# MCU.net
KiCad netlist of a schematic drawn in Altium Designer
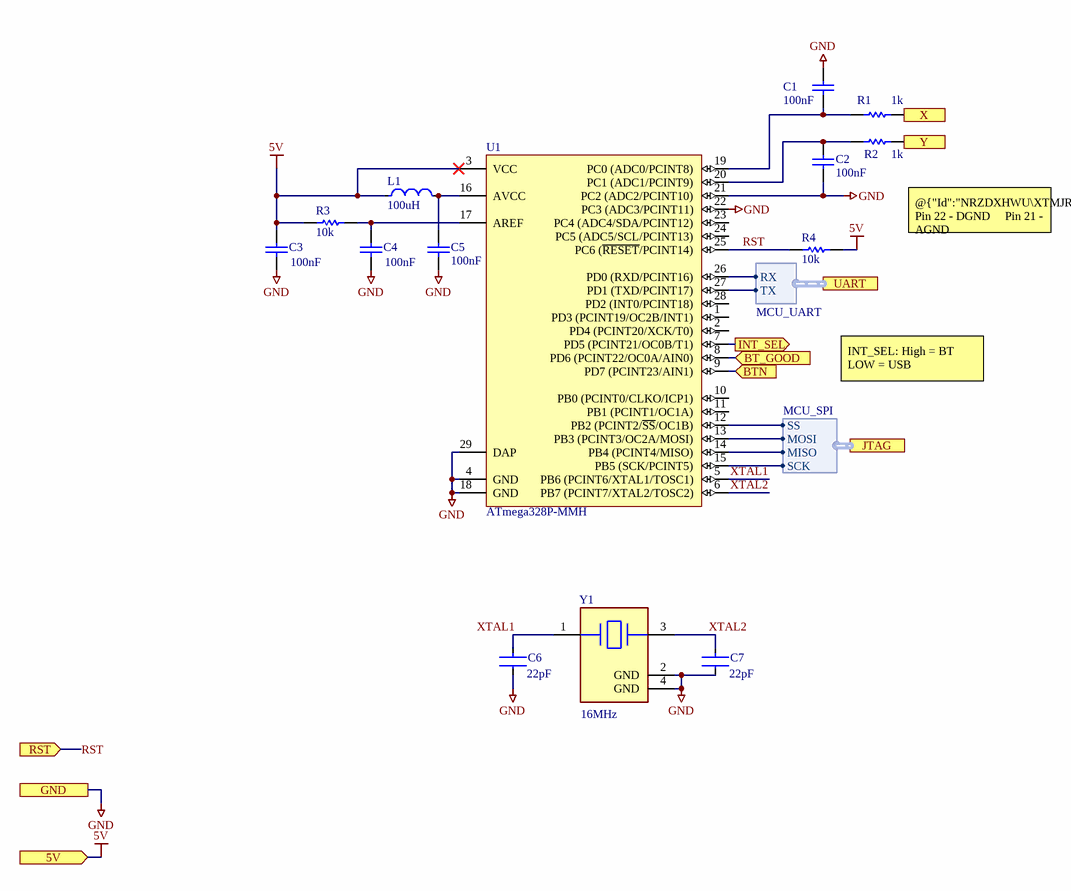
[diagram p0: MCU.SchDoc]

(export (version "E")
  (design (tool "Eeschema 10.0.6"))
  (components
    (comp (ref "C1")
      (value "100nF")
      (footprint "CAPC1005X56X25ML10T15")
      (fields
        (field (name "MANUFACTURER") "AVX Interconnect / Elco")
        (field (name "PART NUMBER") "0402YG104ZAT2A")
      )
      (libsource (lib "Altium Content Vault") (part "CAP"))
    )
    (comp (ref "C2")
      (value "100nF")
      (footprint "CAPC1005X56X25ML10T15")
      (fields
        (field (name "MANUFACTURER") "AVX Interconnect / Elco")
        (field (name "PART NUMBER") "0402YG104ZAT2A")
      )
      (libsource (lib "Altium Content Vault") (part "CAP"))
    )
    (comp (ref "C3")
      (value "100nF")
      (footprint "CAPC1005X56X25ML10T15")
      (fields
        (field (name "MANUFACTURER") "AVX Interconnect / Elco")
        (field (name "PART NUMBER") "0402YG104ZAT2A")
      )
      (libsource (lib "Altium Content Vault") (part "CAP"))
    )
    (comp (ref "C4")
      (value "100nF")
      (footprint "CAPC1005X56X25ML10T15")
      (fields
        (field (name "MANUFACTURER") "AVX Interconnect / Elco")
        (field (name "PART NUMBER") "0402YG104ZAT2A")
      )
      (libsource (lib "Altium Content Vault") (part "CAP"))
    )
    (comp (ref "C5")
      (value "100nF")
      (footprint "CAPC1005X56X25ML10T15")
      (fields
        (field (name "MANUFACTURER") "AVX Interconnect / Elco")
        (field (name "PART NUMBER") "0402YG104ZAT2A")
      )
      (libsource (lib "Altium Content Vault") (part "CAP"))
    )
    (comp (ref "C6")
      (value "C0805C220J5GACTU")
      (footprint "FP-C0805C-DN-MFG")
      (description "Capacitor; Ceramic; Cap; 22.0pF; Tol 5%; SMT; Vol-Rtg 50V; C0G; Tape and Reel")
      (fields
        (field (name "OCTOPART") "https://octopart.com/c0805c220j5gactu-kemet-145470")
        (field (name "MANUFACTURER") "KEMET")
      )
      (libsource (lib "Altium Content Vault") (part "b4654b650e69147ec39a6b967a45e02"))
    )
    (comp (ref "C7")
      (value "C0805C220J5GACTU")
      (footprint "FP-C0805C-DN-MFG")
      (description "Capacitor; Ceramic; Cap; 22.0pF; Tol 5%; SMT; Vol-Rtg 50V; C0G; Tape and Reel")
      (fields
        (field (name "OCTOPART") "https://octopart.com/c0805c220j5gactu-kemet-145470")
        (field (name "MANUFACTURER") "KEMET")
      )
      (libsource (lib "Altium Content Vault") (part "b4654b650e69147ec39a6b967a45e02"))
    )
    (comp (ref "L1")
      (value "100uH")
      (footprint "FP-CB3225-MFG")
      (description "SMD Inductors 100uH ±20% 0.34A 1.82Ω 1210")
      (fields (field (name "TOLERANCE") "20%"))
      (libsource (lib "Altium Content Vault") (part "725321dda6339637d4d059423bc1c3c"))
    )
    (comp (ref "R1")
      (value "1k")
      (footprint "RESC1608X55X25ML10T15")
      (fields (field (name "PART NUMBER") "RT0603BRE071KL") (field (name "MANUFACTURER") "Yageo"))
      (libsource (lib "Altium Content Vault") (part "RES"))
    )
    (comp (ref "R2")
      (value "1k")
      (footprint "RESC1608X55X25ML10T15")
      (fields (field (name "PART NUMBER") "RT0603BRE071KL") (field (name "MANUFACTURER") "Yageo"))
      (libsource (lib "Altium Content Vault") (part "RES"))
    )
    (comp (ref "R3")
      (value "10k")
      (footprint "RESC1005X40X25LL05T05")
      (description "Chip Resistor, 10 KOhm, +/- 1%, 0.1 W, -55 to 155 degC, 0402 (1005 Metric), RoHS, Tape and Reel")
      (fields (field (name "TOLERANCE") "1%") (field (name "MANUFACTURER") "Panasonic"))
      (libsource (lib "Altium Content Vault") (part "RES-2"))
    )
    (comp (ref "R4")
      (value "10k")
      (footprint "RESC1005X40X25LL05T05")
      (description "Chip Resistor, 10 KOhm, +/- 1%, 0.1 W, -55 to 155 degC, 0402 (1005 Metric), RoHS, Tape and Reel")
      (fields (field (name "TOLERANCE") "1%") (field (name "MANUFACTURER") "Panasonic"))
      (libsource (lib "Altium Content Vault") (part "RES-2"))
    )
    (comp (ref "U1")
      (value "ATmega328P-MMH")
      (footprint "28M1_N")
      (libsource (lib "Altium Content Vault") (part "MC-8B-ATM48-IL29"))
    )
    (comp (ref "Y1")
      (value "ABM3B-16.000MHZ-10-1-U-T")
      (footprint "FP-ABM3B-MFG")
      (description "Crystal 16MHz ±10ppm 10pF SMD-4 5mm x 3.2mm")
      (fields (field (name "TOLERANCE") "10ppm"))
      (libsource (lib "Altium Content Vault") (part "48e526d86b7f2615d98721063c72f49"))
    )
  )
  (nets
    (net (code "3") (name "/BTN") (class "Default")
      (node (ref "U1") (pin "9") (pinfunction "PD7_(PCINT23/AIN1)_9") (pintype "bidirectional"))
    )
    (net (code "4") (name "/BT_GOOD") (class "Default")
      (node (ref "U1") (pin "8") (pinfunction "PD6_(PCINT22/OC0A/AIN0)_8") (pintype "bidirectional"))
    )
    (net (code "5") (name "/INT_SEL") (class "Default")
      (node (ref "U1") (pin "7") (pinfunction "PD5_(PCINT21/OC0B/T1)_7") (pintype "bidirectional"))
    )
    (net (code "6") (name "/MISO") (class "Default")
      (node (ref "U1") (pin "14") (pinfunction "PB4_(PCINT4/MISO)_14") (pintype "bidirectional"))
    )
    (net (code "7") (name "/MOSI") (class "Default")
      (node (ref "U1") (pin "13") (pinfunction "PB3_(PCINT3/OC2A/MOSI)_13") (pintype "bidirectional"))
    )
    (net (code "8") (name "/RST") (class "Default")
      (node (ref "R4") (pin "2") (pinfunction "2_2") (pintype "passive"))
      (node (ref "U1") (pin "25") (pinfunction "PC6_(~{RESET}/PCINT14)_25") (pintype "bidirectional"))
    )
    (net (code "9") (name "/RX") (class "Default")
      (node (ref "U1") (pin "26") (pinfunction "PD0_(RXD/PCINT16)_26") (pintype "bidirectional"))
    )
    (net (code "10") (name "/SCK") (class "Default")
      (node (ref "U1") (pin "15") (pinfunction "PB5_(SCK/PCINT5)_15") (pintype "bidirectional"))
    )
    (net (code "11") (name "/SS") (class "Default")
      (node (ref "U1") (pin "12") (pinfunction "PB2_(PCINT2/~{SS}/OC1B)_12") (pintype "bidirectional"))
    )
    (net (code "12") (name "/TX") (class "Default")
      (node (ref "U1") (pin "27") (pinfunction "PD1_(TXD/PCINT17)_27") (pintype "bidirectional"))
    )
    (net (code "13") (name "/X") (class "Default")
      (node (ref "R1") (pin "2") (pinfunction "2_2") (pintype "passive"))
    )
    (net (code "14") (name "/XTAL1") (class "Default")
      (node (ref "C6") (pin "1") (pinfunction "1_1") (pintype "passive"))
      (node (ref "U1") (pin "5") (pinfunction "PB6_(PCINT6/XTAL1/TOSC1)_5") (pintype "bidirectional"))
      (node (ref "Y1") (pin "1") (pinfunction "1_1") (pintype "passive"))
    )
    (net (code "15") (name "/XTAL2") (class "Default")
      (node (ref "C7") (pin "1") (pinfunction "1_1") (pintype "passive"))
      (node (ref "U1") (pin "6") (pinfunction "PB7_(PCINT7/XTAL2/TOSC2)_6") (pintype "bidirectional"))
      (node (ref "Y1") (pin "3") (pinfunction "3_3") (pintype "passive"))
    )
    (net (code "16") (name "/Y") (class "Default")
      (node (ref "R2") (pin "2") (pinfunction "2_2") (pintype "passive"))
    )
    (net (code "19") (name "5V") (class "Default")
      (node (ref "C3") (pin "2") (pinfunction "2_2") (pintype "passive"))
      (node (ref "L1") (pin "1") (pinfunction "1_1") (pintype "passive"))
      (node (ref "R3") (pin "2") (pinfunction "2_2") (pintype "passive"))
      (node (ref "R4") (pin "1") (pinfunction "1_1") (pintype "passive"))
      (node (ref "U1") (pin "3") (pinfunction "VCC_3") (pintype "power_in"))
    )
    (net (code "20") (name "GND") (class "Default")
      (node (ref "C1") (pin "2") (pinfunction "2_2") (pintype "passive"))
      (node (ref "C2") (pin "2") (pinfunction "2_2") (pintype "passive"))
      (node (ref "C3") (pin "1") (pinfunction "1_1") (pintype "passive"))
      (node (ref "C4") (pin "1") (pinfunction "1_1") (pintype "passive"))
      (node (ref "C5") (pin "2") (pinfunction "2_2") (pintype "passive"))
      (node (ref "C6") (pin "2") (pinfunction "2_2") (pintype "passive"))
      (node (ref "C7") (pin "2") (pinfunction "2_2") (pintype "passive"))
      (node (ref "U1") (pin "18") (pinfunction "GND_18") (pintype "power_in"))
      (node (ref "U1") (pin "21") (pinfunction "PC2_(ADC2/PCINT10)_21") (pintype "bidirectional"))
      (node (ref "U1") (pin "22") (pinfunction "PC3_(ADC3/PCINT11)_22") (pintype "bidirectional"))
      (node (ref "U1") (pin "29") (pinfunction "DAP_29") (pintype "power_in"))
      (node (ref "U1") (pin "4") (pinfunction "GND_4") (pintype "power_in"))
      (node (ref "Y1") (pin "2") (pinfunction "GND_2") (pintype "power_in"))
      (node (ref "Y1") (pin "4") (pinfunction "GND_4") (pintype "power_in"))
    )
    (net (code "21") (name "Net-(U1-AREF)") (class "Default")
      (node (ref "C4") (pin "2") (pinfunction "2_2") (pintype "passive"))
      (node (ref "R3") (pin "1") (pinfunction "1_1") (pintype "passive"))
      (node (ref "U1") (pin "17") (pinfunction "AREF_17") (pintype "power_in"))
    )
    (net (code "22") (name "Net-(U1-AVCC)") (class "Default")
      (node (ref "C5") (pin "1") (pinfunction "1_1") (pintype "passive"))
      (node (ref "L1") (pin "2") (pinfunction "2_2") (pintype "passive"))
      (node (ref "U1") (pin "16") (pinfunction "AVCC_16") (pintype "power_in"))
    )
    (net (code "23") (name "Net-(U1-PC0_(ADC0{slash}PCINT8))") (class "Default")
      (node (ref "C1") (pin "1") (pinfunction "1_1") (pintype "passive"))
      (node (ref "R1") (pin "1") (pinfunction "1_1") (pintype "passive"))
      (node (ref "U1") (pin "19") (pinfunction "PC0_(ADC0/PCINT8)_19") (pintype "bidirectional"))
    )
    (net (code "24") (name "Net-(U1-PC1_(ADC1{slash}PCINT9))") (class "Default")
      (node (ref "C2") (pin "1") (pinfunction "1_1") (pintype "passive"))
      (node (ref "R2") (pin "1") (pinfunction "1_1") (pintype "passive"))
      (node (ref "U1") (pin "20") (pinfunction "PC1_(ADC1/PCINT9)_20") (pintype "bidirectional"))
    )
    (net (code "25") (name "unconnected-(U1-PB0_(PCINT0{slash}CLKO{slash}ICP1)-Pad10)") (class "Default")
      (node (ref "U1") (pin "10") (pinfunction "PB0_(PCINT0/CLKO/ICP1)_10") (pintype "bidirectional"))
    )
    (net (code "26") (name "unconnected-(U1-PB1_(PCINT1{slash}OC1A)-Pad11)") (class "Default")
      (node (ref "U1") (pin "11") (pinfunction "PB1_(PCINT1/OC1A)_11") (pintype "bidirectional"))
    )
    (net (code "27") (name "unconnected-(U1-PC4_(ADC4{slash}SDA{slash}PCINT12)-Pad23)") (class "Default")
      (node (ref "U1") (pin "23") (pinfunction "PC4_(ADC4/SDA/PCINT12)_23") (pintype "bidirectional"))
    )
    (net (code "28") (name "unconnected-(U1-PC5_(ADC5{slash}SCL{slash}PCINT13)-Pad24)") (class "Default")
      (node (ref "U1") (pin "24") (pinfunction "PC5_(ADC5/SCL/PCINT13)_24") (pintype "bidirectional"))
    )
    (net (code "29") (name "unconnected-(U1-PD2_(INT0{slash}PCINT18)-Pad28)") (class "Default")
      (node (ref "U1") (pin "28") (pinfunction "PD2_(INT0/PCINT18)_28") (pintype "bidirectional"))
    )
    (net (code "30") (name "unconnected-(U1-PD3_(PCINT19{slash}OC2B{slash}INT1)-Pad1)") (class "Default")
      (node (ref "U1") (pin "1") (pinfunction "PD3_(PCINT19/OC2B/INT1)_1") (pintype "bidirectional"))
    )
    (net (code "31") (name "unconnected-(U1-PD4_(PCINT20{slash}XCK{slash}T0)-Pad2)") (class "Default")
      (node (ref "U1") (pin "2") (pinfunction "PD4_(PCINT20/XCK/T0)_2") (pintype "bidirectional"))
    )
  )
)
